# MP-Portenta.net
KiCad netlist of a schematic drawn in Altium Designer
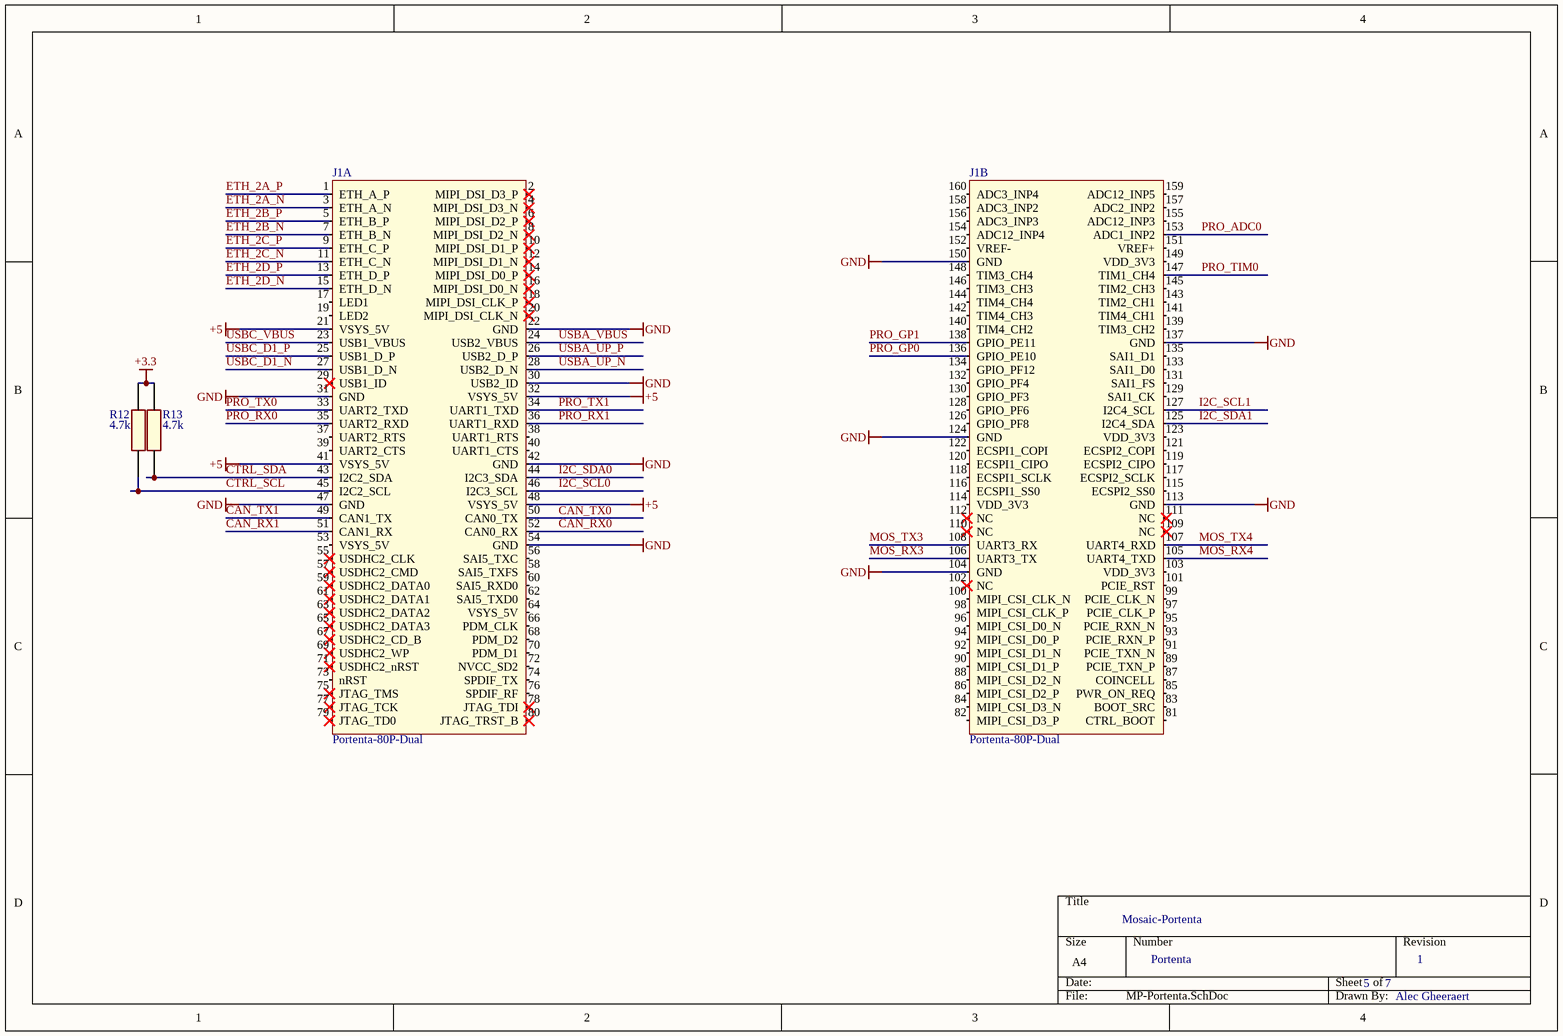
[diagram p0: MP-Portenta.SchDoc]

(export (version "E")
  (design (tool "Eeschema 10.0.6"))
  (components
    (comp (ref "J1")
      (value "Portenta-80P-Dual")
      (footprint "HRS_DF40C-80DP-0.4V(51)")
      (description "80 Pin Arduino Pro")
      (fields (field (name "MANUFACTURER") "Arduino"))
      (libsource (lib "Ghrt") (part "Portenta-80P-Dual"))
    )
    (comp (ref "R12")
      (value "4.7k")
      (footprint "RESC1005X40N")
      (description "0402I 4.7k")
      (fields (field (name "MANUFACTURER") "Walsin") (field (name "TOLERANCE") "1%"))
      (libsource (lib "") (part "WR04X4701FTL_1"))
    )
    (comp (ref "R13")
      (value "4.7k")
      (footprint "RESC1005X40N")
      (description "0402I 4.7k")
      (fields (field (name "MANUFACTURER") "Walsin") (field (name "TOLERANCE") "1%"))
      (libsource (lib "Ghrt") (part "WR04X4701FTL"))
    )
  )
  (nets
    (net (code "1") (name "+3.3") (class "Default")
      (node (ref "R12") (pin "2") (pinfunction "2_2") (pintype "passive"))
      (node (ref "R13") (pin "1") (pinfunction "1_1") (pintype "passive"))
    )
    (net (code "2") (name "+5") (class "Default")
      (node (ref "J1") (pin "21") (pinfunction "VSYS_5V_21") (pintype "passive"))
      (node (ref "J1") (pin "32") (pinfunction "VSYS_5V_32") (pintype "passive"))
      (node (ref "J1") (pin "41") (pinfunction "VSYS_5V_41") (pintype "passive"))
      (node (ref "J1") (pin "48") (pinfunction "VSYS_5V_48") (pintype "passive"))
    )
    (net (code "3") (name "/CAN_RX0") (class "Default")
      (node (ref "J1") (pin "52") (pinfunction "CAN0_RX_52") (pintype "passive"))
    )
    (net (code "4") (name "/CAN_RX1") (class "Default")
      (node (ref "J1") (pin "51") (pinfunction "CAN1_RX_51") (pintype "passive"))
    )
    (net (code "5") (name "/CAN_TX0") (class "Default")
      (node (ref "J1") (pin "50") (pinfunction "CAN0_TX_50") (pintype "passive"))
    )
    (net (code "6") (name "/CAN_TX1") (class "Default")
      (node (ref "J1") (pin "49") (pinfunction "CAN1_TX_49") (pintype "passive"))
    )
    (net (code "7") (name "/CTRL_SCL") (class "Default")
      (node (ref "J1") (pin "45") (pinfunction "I2C2_SCL_45") (pintype "passive"))
      (node (ref "R12") (pin "1") (pinfunction "1_1") (pintype "passive"))
    )
    (net (code "8") (name "/CTRL_SDA") (class "Default")
      (node (ref "J1") (pin "43") (pinfunction "I2C2_SDA_43") (pintype "passive"))
      (node (ref "R13") (pin "2") (pinfunction "2_2") (pintype "passive"))
    )
    (net (code "9") (name "/ETH_2A_N") (class "Default")
      (node (ref "J1") (pin "3") (pinfunction "ETH_A_N_3") (pintype "passive"))
    )
    (net (code "10") (name "/ETH_2A_P") (class "Default")
      (node (ref "J1") (pin "1") (pinfunction "ETH_A_P_1") (pintype "passive"))
    )
    (net (code "11") (name "/ETH_2B_N") (class "Default")
      (node (ref "J1") (pin "7") (pinfunction "ETH_B_N_7") (pintype "passive"))
    )
    (net (code "12") (name "/ETH_2B_P") (class "Default")
      (node (ref "J1") (pin "5") (pinfunction "ETH_B_P_5") (pintype "passive"))
    )
    (net (code "13") (name "/ETH_2C_N") (class "Default")
      (node (ref "J1") (pin "11") (pinfunction "ETH_C_N_11") (pintype "passive"))
    )
    (net (code "14") (name "/ETH_2C_P") (class "Default")
      (node (ref "J1") (pin "9") (pinfunction "ETH_C_P_9") (pintype "passive"))
    )
    (net (code "15") (name "/ETH_2D_N") (class "Default")
      (node (ref "J1") (pin "15") (pinfunction "ETH_D_N_15") (pintype "passive"))
    )
    (net (code "16") (name "/ETH_2D_P") (class "Default")
      (node (ref "J1") (pin "13") (pinfunction "ETH_D_P_13") (pintype "passive"))
    )
    (net (code "17") (name "/I2C_SCL0") (class "Default")
      (node (ref "J1") (pin "46") (pinfunction "I2C3_SCL_46") (pintype "passive"))
    )
    (net (code "18") (name "/I2C_SCL1") (class "Default")
      (node (ref "J1") (pin "127") (pinfunction "I2C4_SCL_127") (pintype "passive"))
    )
    (net (code "19") (name "/I2C_SDA0") (class "Default")
      (node (ref "J1") (pin "44") (pinfunction "I2C3_SDA_44") (pintype "passive"))
    )
    (net (code "20") (name "/I2C_SDA1") (class "Default")
      (node (ref "J1") (pin "125") (pinfunction "I2C4_SDA_125") (pintype "passive"))
    )
    (net (code "21") (name "/MOS_RX3") (class "Default")
      (node (ref "J1") (pin "106") (pinfunction "UART3_TX_106") (pintype "passive"))
    )
    (net (code "22") (name "/MOS_RX4") (class "Default")
      (node (ref "J1") (pin "105") (pinfunction "UART4_TXD_105") (pintype "passive"))
    )
    (net (code "23") (name "/MOS_TX3") (class "Default")
      (node (ref "J1") (pin "108") (pinfunction "UART3_RX_108") (pintype "passive"))
    )
    (net (code "24") (name "/MOS_TX4") (class "Default")
      (node (ref "J1") (pin "107") (pinfunction "UART4_RXD_107") (pintype "passive"))
    )
    (net (code "25") (name "/PRO_ADC0") (class "Default")
      (node (ref "J1") (pin "153") (pinfunction "ADC1_INP2_153") (pintype "passive"))
    )
    (net (code "26") (name "/PRO_GP0") (class "Default")
      (node (ref "J1") (pin "136") (pinfunction "GPIO_PE10_136") (pintype "passive"))
    )
    (net (code "27") (name "/PRO_GP1") (class "Default")
      (node (ref "J1") (pin "138") (pinfunction "GPIO_PE11_138") (pintype "passive"))
    )
    (net (code "28") (name "/PRO_RX0") (class "Default")
      (node (ref "J1") (pin "35") (pinfunction "UART2_RXD_35") (pintype "passive"))
    )
    (net (code "29") (name "/PRO_RX1") (class "Default")
      (node (ref "J1") (pin "36") (pinfunction "UART1_RXD_36") (pintype "passive"))
    )
    (net (code "30") (name "/PRO_TIM0") (class "Default")
      (node (ref "J1") (pin "147") (pinfunction "TIM1_CH4_147") (pintype "passive"))
    )
    (net (code "31") (name "/PRO_TX0") (class "Default")
      (node (ref "J1") (pin "33") (pinfunction "UART2_TXD_33") (pintype "passive"))
    )
    (net (code "32") (name "/PRO_TX1") (class "Default")
      (node (ref "J1") (pin "34") (pinfunction "UART1_TXD_34") (pintype "passive"))
    )
    (net (code "33") (name "/USBA_UP_N") (class "Default")
      (node (ref "J1") (pin "28") (pinfunction "USB2_D_N_28") (pintype "passive"))
    )
    (net (code "34") (name "/USBA_UP_P") (class "Default")
      (node (ref "J1") (pin "26") (pinfunction "USB2_D_P_26") (pintype "passive"))
    )
    (net (code "35") (name "/USBA_VBUS") (class "Default")
      (node (ref "J1") (pin "24") (pinfunction "USB2_VBUS_24") (pintype "passive"))
    )
    (net (code "36") (name "/USBC_D1_N") (class "Default")
      (node (ref "J1") (pin "27") (pinfunction "USB1_D_N_27") (pintype "passive"))
    )
    (net (code "37") (name "/USBC_D1_P") (class "Default")
      (node (ref "J1") (pin "25") (pinfunction "USB1_D_P_25") (pintype "passive"))
    )
    (net (code "38") (name "/USBC_VBUS") (class "Default")
      (node (ref "J1") (pin "23") (pinfunction "USB1_VBUS_23") (pintype "passive"))
    )
    (net (code "39") (name "GND") (class "Default")
      (node (ref "J1") (pin "104") (pinfunction "GND_104") (pintype "passive"))
      (node (ref "J1") (pin "113") (pinfunction "GND_113") (pintype "passive"))
      (node (ref "J1") (pin "124") (pinfunction "GND_124") (pintype "passive"))
      (node (ref "J1") (pin "137") (pinfunction "GND_137") (pintype "passive"))
      (node (ref "J1") (pin "150") (pinfunction "GND_150") (pintype "passive"))
      (node (ref "J1") (pin "22") (pinfunction "GND_22") (pintype "passive"))
      (node (ref "J1") (pin "30") (pinfunction "USB2_ID_30") (pintype "passive"))
      (node (ref "J1") (pin "31") (pinfunction "GND_31") (pintype "passive"))
      (node (ref "J1") (pin "42") (pinfunction "GND_42") (pintype "passive"))
      (node (ref "J1") (pin "47") (pinfunction "GND_47") (pintype "passive"))
      (node (ref "J1") (pin "54") (pinfunction "GND_54") (pintype "passive"))
    )
    (net (code "40") (name "unconnected-(J1A-JTAG_TCK-Pad77)") (class "Default")
      (node (ref "J1") (pin "77") (pinfunction "JTAG_TCK_77") (pintype "passive+no_connect"))
    )
    (net (code "41") (name "unconnected-(J1A-JTAG_TD0-Pad79)") (class "Default")
      (node (ref "J1") (pin "79") (pinfunction "JTAG_TD0_79") (pintype "passive+no_connect"))
    )
    (net (code "42") (name "unconnected-(J1A-JTAG_TDI-Pad78)") (class "Default")
      (node (ref "J1") (pin "78") (pinfunction "JTAG_TDI_78") (pintype "passive+no_connect"))
    )
    (net (code "43") (name "unconnected-(J1A-JTAG_TMS-Pad75)") (class "Default")
      (node (ref "J1") (pin "75") (pinfunction "JTAG_TMS_75") (pintype "passive+no_connect"))
    )
    (net (code "44") (name "unconnected-(J1A-JTAG_TRST_B-Pad80)") (class "Default")
      (node (ref "J1") (pin "80") (pinfunction "JTAG_TRST_B_80") (pintype "passive+no_connect"))
    )
    (net (code "45") (name "unconnected-(J1A-LED1-Pad17)") (class "Default")
      (node (ref "J1") (pin "17") (pinfunction "LED1_17") (pintype "passive"))
    )
    (net (code "46") (name "unconnected-(J1A-LED2-Pad19)") (class "Default")
      (node (ref "J1") (pin "19") (pinfunction "LED2_19") (pintype "passive"))
    )
    (net (code "47") (name "unconnected-(J1A-MIPI_DSI_CLK_N-Pad20)") (class "Default")
      (node (ref "J1") (pin "20") (pinfunction "MIPI_DSI_CLK_N_20") (pintype "passive+no_connect"))
    )
    (net (code "48") (name "unconnected-(J1A-MIPI_DSI_CLK_P-Pad18)") (class "Default")
      (node (ref "J1") (pin "18") (pinfunction "MIPI_DSI_CLK_P_18") (pintype "passive+no_connect"))
    )
    (net (code "49") (name "unconnected-(J1A-MIPI_DSI_D0_N-Pad16)") (class "Default")
      (node (ref "J1") (pin "16") (pinfunction "MIPI_DSI_D0_N_16") (pintype "passive+no_connect"))
    )
    (net (code "50") (name "unconnected-(J1A-MIPI_DSI_D0_P-Pad14)") (class "Default")
      (node (ref "J1") (pin "14") (pinfunction "MIPI_DSI_D0_P_14") (pintype "passive+no_connect"))
    )
    (net (code "51") (name "unconnected-(J1A-MIPI_DSI_D1_N-Pad12)") (class "Default")
      (node (ref "J1") (pin "12") (pinfunction "MIPI_DSI_D1_N_12") (pintype "passive+no_connect"))
    )
    (net (code "52") (name "unconnected-(J1A-MIPI_DSI_D1_P-Pad10)") (class "Default")
      (node (ref "J1") (pin "10") (pinfunction "MIPI_DSI_D1_P_10") (pintype "passive+no_connect"))
    )
    (net (code "53") (name "unconnected-(J1A-MIPI_DSI_D2_N-Pad8)") (class "Default")
      (node (ref "J1") (pin "8") (pinfunction "MIPI_DSI_D2_N_8") (pintype "passive+no_connect"))
    )
    (net (code "54") (name "unconnected-(J1A-MIPI_DSI_D2_P-Pad6)") (class "Default")
      (node (ref "J1") (pin "6") (pinfunction "MIPI_DSI_D2_P_6") (pintype "passive+no_connect"))
    )
    (net (code "55") (name "unconnected-(J1A-MIPI_DSI_D3_N-Pad4)") (class "Default")
      (node (ref "J1") (pin "4") (pinfunction "MIPI_DSI_D3_N_4") (pintype "passive+no_connect"))
    )
    (net (code "56") (name "unconnected-(J1A-MIPI_DSI_D3_P-Pad2)") (class "Default")
      (node (ref "J1") (pin "2") (pinfunction "MIPI_DSI_D3_P_2") (pintype "passive+no_connect"))
    )
    (net (code "57") (name "unconnected-(J1A-NVCC_SD2-Pad72)") (class "Default")
      (node (ref "J1") (pin "72") (pinfunction "NVCC_SD2_72") (pintype "passive"))
    )
    (net (code "58") (name "unconnected-(J1A-PDM_CLK-Pad66)") (class "Default")
      (node (ref "J1") (pin "66") (pinfunction "PDM_CLK_66") (pintype "passive"))
    )
    (net (code "59") (name "unconnected-(J1A-PDM_D1-Pad70)") (class "Default")
      (node (ref "J1") (pin "70") (pinfunction "PDM_D1_70") (pintype "passive"))
    )
    (net (code "60") (name "unconnected-(J1A-PDM_D2-Pad68)") (class "Default")
      (node (ref "J1") (pin "68") (pinfunction "PDM_D2_68") (pintype "passive"))
    )
    (net (code "61") (name "unconnected-(J1A-SAI5_RXD0-Pad60)") (class "Default")
      (node (ref "J1") (pin "60") (pinfunction "SAI5_RXD0_60") (pintype "passive"))
    )
    (net (code "62") (name "unconnected-(J1A-SAI5_TXC-Pad56)") (class "Default")
      (node (ref "J1") (pin "56") (pinfunction "SAI5_TXC_56") (pintype "passive"))
    )
    (net (code "63") (name "unconnected-(J1A-SAI5_TXD0-Pad62)") (class "Default")
      (node (ref "J1") (pin "62") (pinfunction "SAI5_TXD0_62") (pintype "passive"))
    )
    (net (code "64") (name "unconnected-(J1A-SAI5_TXFS-Pad58)") (class "Default")
      (node (ref "J1") (pin "58") (pinfunction "SAI5_TXFS_58") (pintype "passive"))
    )
    (net (code "65") (name "unconnected-(J1A-SPDIF_RF-Pad76)") (class "Default")
      (node (ref "J1") (pin "76") (pinfunction "SPDIF_RF_76") (pintype "passive"))
    )
    (net (code "66") (name "unconnected-(J1A-SPDIF_TX-Pad74)") (class "Default")
      (node (ref "J1") (pin "74") (pinfunction "SPDIF_TX_74") (pintype "passive"))
    )
    (net (code "67") (name "unconnected-(J1A-UART1_CTS-Pad40)") (class "Default")
      (node (ref "J1") (pin "40") (pinfunction "UART1_CTS_40") (pintype "passive"))
    )
    (net (code "68") (name "unconnected-(J1A-UART1_RTS-Pad38)") (class "Default")
      (node (ref "J1") (pin "38") (pinfunction "UART1_RTS_38") (pintype "passive"))
    )
    (net (code "69") (name "unconnected-(J1A-UART2_CTS-Pad39)") (class "Default")
      (node (ref "J1") (pin "39") (pinfunction "UART2_CTS_39") (pintype "passive"))
    )
    (net (code "70") (name "unconnected-(J1A-UART2_RTS-Pad37)") (class "Default")
      (node (ref "J1") (pin "37") (pinfunction "UART2_RTS_37") (pintype "passive"))
    )
    (net (code "71") (name "unconnected-(J1A-USB1_ID-Pad29)") (class "Default")
      (node (ref "J1") (pin "29") (pinfunction "USB1_ID_29") (pintype "passive+no_connect"))
    )
    (net (code "72") (name "unconnected-(J1A-USDHC2_CD_B-Pad67)") (class "Default")
      (node (ref "J1") (pin "67") (pinfunction "USDHC2_CD_B_67") (pintype "passive+no_connect"))
    )
    (net (code "73") (name "unconnected-(J1A-USDHC2_CLK-Pad55)") (class "Default")
      (node (ref "J1") (pin "55") (pinfunction "USDHC2_CLK_55") (pintype "passive+no_connect"))
    )
    (net (code "74") (name "unconnected-(J1A-USDHC2_CMD-Pad57)") (class "Default")
      (node (ref "J1") (pin "57") (pinfunction "USDHC2_CMD_57") (pintype "passive+no_connect"))
    )
    (net (code "75") (name "unconnected-(J1A-USDHC2_DATA0-Pad59)") (class "Default")
      (node (ref "J1") (pin "59") (pinfunction "USDHC2_DATA0_59") (pintype "passive+no_connect"))
    )
    (net (code "76") (name "unconnected-(J1A-USDHC2_DATA1-Pad61)") (class "Default")
      (node (ref "J1") (pin "61") (pinfunction "USDHC2_DATA1_61") (pintype "passive+no_connect"))
    )
    (net (code "77") (name "unconnected-(J1A-USDHC2_DATA2-Pad63)") (class "Default")
      (node (ref "J1") (pin "63") (pinfunction "USDHC2_DATA2_63") (pintype "passive+no_connect"))
    )
    (net (code "78") (name "unconnected-(J1A-USDHC2_DATA3-Pad65)") (class "Default")
      (node (ref "J1") (pin "65") (pinfunction "USDHC2_DATA3_65") (pintype "passive+no_connect"))
    )
    (net (code "79") (name "unconnected-(J1A-USDHC2_WP-Pad69)") (class "Default")
      (node (ref "J1") (pin "69") (pinfunction "USDHC2_WP_69") (pintype "passive+no_connect"))
    )
    (net (code "80") (name "unconnected-(J1A-USDHC2_nRST-Pad71)") (class "Default")
      (node (ref "J1") (pin "71") (pinfunction "USDHC2_nRST_71") (pintype "passive+no_connect"))
    )
    (net (code "81") (name "unconnected-(J1A-VSYS_5V-Pad53)") (class "Default")
      (node (ref "J1") (pin "53") (pinfunction "VSYS_5V_53") (pintype "passive"))
    )
    (net (code "82") (name "unconnected-(J1A-VSYS_5V-Pad64)") (class "Default")
      (node (ref "J1") (pin "64") (pinfunction "VSYS_5V_64") (pintype "passive"))
    )
    (net (code "83") (name "unconnected-(J1A-nRST-Pad73)") (class "Default")
      (node (ref "J1") (pin "73") (pinfunction "nRST_73") (pintype "passive"))
    )
    (net (code "84") (name "unconnected-(J1B-ADC2_INP2-Pad157)") (class "Default")
      (node (ref "J1") (pin "157") (pinfunction "ADC2_INP2_157") (pintype "passive"))
    )
    (net (code "85") (name "unconnected-(J1B-ADC3_INP2-Pad158)") (class "Default")
      (node (ref "J1") (pin "158") (pinfunction "ADC3_INP2_158") (pintype "passive"))
    )
    (net (code "86") (name "unconnected-(J1B-ADC3_INP3-Pad156)") (class "Default")
      (node (ref "J1") (pin "156") (pinfunction "ADC3_INP3_156") (pintype "passive"))
    )
    (net (code "87") (name "unconnected-(J1B-ADC3_INP4-Pad160)") (class "Default")
      (node (ref "J1") (pin "160") (pinfunction "ADC3_INP4_160") (pintype "passive"))
    )
    (net (code "88") (name "unconnected-(J1B-ADC12_INP3-Pad155)") (class "Default")
      (node (ref "J1") (pin "155") (pinfunction "ADC12_INP3_155") (pintype "passive"))
    )
    (net (code "89") (name "unconnected-(J1B-ADC12_INP4-Pad154)") (class "Default")
      (node (ref "J1") (pin "154") (pinfunction "ADC12_INP4_154") (pintype "passive"))
    )
    (net (code "90") (name "unconnected-(J1B-ADC12_INP5-Pad159)") (class "Default")
      (node (ref "J1") (pin "159") (pinfunction "ADC12_INP5_159") (pintype "passive"))
    )
    (net (code "91") (name "unconnected-(J1B-BOOT_SRC-Pad83)") (class "Default")
      (node (ref "J1") (pin "83") (pinfunction "BOOT_SRC_83") (pintype "passive"))
    )
    (net (code "92") (name "unconnected-(J1B-COINCELL-Pad87)") (class "Default")
      (node (ref "J1") (pin "87") (pinfunction "COINCELL_87") (pintype "passive"))
    )
    (net (code "93") (name "unconnected-(J1B-CTRL_BOOT-Pad81)") (class "Default")
      (node (ref "J1") (pin "81") (pinfunction "CTRL_BOOT_81") (pintype "passive"))
    )
    (net (code "94") (name "unconnected-(J1B-ECSPI1_CIPO-Pad120)") (class "Default")
      (node (ref "J1") (pin "120") (pinfunction "ECSPI1_CIPO_120") (pintype "passive"))
    )
    (net (code "95") (name "unconnected-(J1B-ECSPI1_COPI-Pad122)") (class "Default")
      (node (ref "J1") (pin "122") (pinfunction "ECSPI1_COPI_122") (pintype "passive"))
    )
    (net (code "96") (name "unconnected-(J1B-ECSPI1_SCLK-Pad118)") (class "Default")
      (node (ref "J1") (pin "118") (pinfunction "ECSPI1_SCLK_118") (pintype "passive"))
    )
    (net (code "97") (name "unconnected-(J1B-ECSPI1_SS0-Pad116)") (class "Default")
      (node (ref "J1") (pin "116") (pinfunction "ECSPI1_SS0_116") (pintype "passive"))
    )
    (net (code "98") (name "unconnected-(J1B-ECSPI2_CIPO-Pad119)") (class "Default")
      (node (ref "J1") (pin "119") (pinfunction "ECSPI2_CIPO_119") (pintype "passive"))
    )
    (net (code "99") (name "unconnected-(J1B-ECSPI2_COPI-Pad121)") (class "Default")
      (node (ref "J1") (pin "121") (pinfunction "ECSPI2_COPI_121") (pintype "passive"))
    )
    (net (code "100") (name "unconnected-(J1B-ECSPI2_SCLK-Pad117)") (class "Default")
      (node (ref "J1") (pin "117") (pinfunction "ECSPI2_SCLK_117") (pintype "passive"))
    )
    (net (code "101") (name "unconnected-(J1B-ECSPI2_SS0-Pad115)") (class "Default")
      (node (ref "J1") (pin "115") (pinfunction "ECSPI2_SS0_115") (pintype "passive"))
    )
    (net (code "102") (name "unconnected-(J1B-GPIO_PF3-Pad130)") (class "Default")
      (node (ref "J1") (pin "130") (pinfunction "GPIO_PF3_130") (pintype "passive"))
    )
    (net (code "103") (name "unconnected-(J1B-GPIO_PF4-Pad132)") (class "Default")
      (node (ref "J1") (pin "132") (pinfunction "GPIO_PF4_132") (pintype "passive"))
    )
    (net (code "104") (name "unconnected-(J1B-GPIO_PF6-Pad128)") (class "Default")
      (node (ref "J1") (pin "128") (pinfunction "GPIO_PF6_128") (pintype "passive"))
    )
    (net (code "105") (name "unconnected-(J1B-GPIO_PF8-Pad126)") (class "Default")
      (node (ref "J1") (pin "126") (pinfunction "GPIO_PF8_126") (pintype "passive"))
    )
    (net (code "106") (name "unconnected-(J1B-GPIO_PF12-Pad134)") (class "Default")
      (node (ref "J1") (pin "134") (pinfunction "GPIO_PF12_134") (pintype "passive"))
    )
    (net (code "107") (name "unconnected-(J1B-MIPI_CSI_CLK_N-Pad100)") (class "Default")
      (node (ref "J1") (pin "100") (pinfunction "MIPI_CSI_CLK_N_100") (pintype "passive"))
    )
    (net (code "108") (name "unconnected-(J1B-MIPI_CSI_CLK_P-Pad98)") (class "Default")
      (node (ref "J1") (pin "98") (pinfunction "MIPI_CSI_CLK_P_98") (pintype "passive"))
    )
    (net (code "109") (name "unconnected-(J1B-MIPI_CSI_D0_N-Pad96)") (class "Default")
      (node (ref "J1") (pin "96") (pinfunction "MIPI_CSI_D0_N_96") (pintype "passive"))
    )
    (net (code "110") (name "unconnected-(J1B-MIPI_CSI_D0_P-Pad94)") (class "Default")
      (node (ref "J1") (pin "94") (pinfunction "MIPI_CSI_D0_P_94") (pintype "passive"))
    )
    (net (code "111") (name "unconnected-(J1B-MIPI_CSI_D1_N-Pad92)") (class "Default")
      (node (ref "J1") (pin "92") (pinfunction "MIPI_CSI_D1_N_92") (pintype "passive"))
    )
    (net (code "112") (name "unconnected-(J1B-MIPI_CSI_D1_P-Pad90)") (class "Default")
      (node (ref "J1") (pin "90") (pinfunction "MIPI_CSI_D1_P_90") (pintype "passive"))
    )
    (net (code "113") (name "unconnected-(J1B-MIPI_CSI_D2_N-Pad88)") (class "Default")
      (node (ref "J1") (pin "88") (pinfunction "MIPI_CSI_D2_N_88") (pintype "passive"))
    )
    (net (code "114") (name "unconnected-(J1B-MIPI_CSI_D2_P-Pad86)") (class "Default")
      (node (ref "J1") (pin "86") (pinfunction "MIPI_CSI_D2_P_86") (pintype "passive"))
    )
    (net (code "115") (name "unconnected-(J1B-MIPI_CSI_D3_N-Pad84)") (class "Default")
      (node (ref "J1") (pin "84") (pinfunction "MIPI_CSI_D3_N_84") (pintype "passive"))
    )
    (net (code "116") (name "unconnected-(J1B-MIPI_CSI_D3_P-Pad82)") (class "Default")
      (node (ref "J1") (pin "82") (pinfunction "MIPI_CSI_D3_P_82") (pintype "passive"))
    )
    (net (code "117") (name "unconnected-(J1B-NC-Pad102)") (class "Default")
      (node (ref "J1") (pin "102") (pinfunction "NC_102") (pintype "passive+no_connect"))
    )
    (net (code "118") (name "unconnected-(J1B-NC-Pad109)") (class "Default")
      (node (ref "J1") (pin "109") (pinfunction "NC_109") (pintype "passive+no_connect"))
    )
    (net (code "119") (name "unconnected-(J1B-NC-Pad110)") (class "Default")
      (node (ref "J1") (pin "110") (pinfunction "NC_110") (pintype "passive+no_connect"))
    )
    (net (code "120") (name "unconnected-(J1B-NC-Pad111)") (class "Default")
      (node (ref "J1") (pin "111") (pinfunction "NC_111") (pintype "passive+no_connect"))
    )
    (net (code "121") (name "unconnected-(J1B-NC-Pad112)") (class "Default")
      (node (ref "J1") (pin "112") (pinfunction "NC_112") (pintype "passive+no_connect"))
    )
    (net (code "122") (name "unconnected-(J1B-PCIE_CLK_N-Pad99)") (class "Default")
      (node (ref "J1") (pin "99") (pinfunction "PCIE_CLK_N_99") (pintype "passive"))
    )
    (net (code "123") (name "unconnected-(J1B-PCIE_CLK_P-Pad97)") (class "Default")
      (node (ref "J1") (pin "97") (pinfunction "PCIE_CLK_P_97") (pintype "passive"))
    )
    (net (code "124") (name "unconnected-(J1B-PCIE_RST-Pad101)") (class "Default")
      (node (ref "J1") (pin "101") (pinfunction "PCIE_RST_101") (pintype "passive"))
    )
    (net (code "125") (name "unconnected-(J1B-PCIE_RXN_N-Pad95)") (class "Default")
      (node (ref "J1") (pin "95") (pinfunction "PCIE_RXN_N_95") (pintype "passive"))
    )
    (net (code "126") (name "unconnected-(J1B-PCIE_RXN_P-Pad93)") (class "Default")
      (node (ref "J1") (pin "93") (pinfunction "PCIE_RXN_P_93") (pintype "passive"))
    )
    (net (code "127") (name "unconnected-(J1B-PCIE_TXN_N-Pad91)") (class "Default")
      (node (ref "J1") (pin "91") (pinfunction "PCIE_TXN_N_91") (pintype "passive"))
    )
    (net (code "128") (name "unconnected-(J1B-PCIE_TXN_P-Pad89)") (class "Default")
      (node (ref "J1") (pin "89") (pinfunction "PCIE_TXN_P_89") (pintype "passive"))
    )
    (net (code "129") (name "unconnected-(J1B-PWR_ON_REQ-Pad85)") (class "Default")
      (node (ref "J1") (pin "85") (pinfunction "PWR_ON_REQ_85") (pintype "passive"))
    )
    (net (code "130") (name "unconnected-(J1B-SAI1_CK-Pad129)") (class "Default")
      (node (ref "J1") (pin "129") (pinfunction "SAI1_CK_129") (pintype "passive"))
    )
    (net (code "131") (name "unconnected-(J1B-SAI1_D0-Pad133)") (class "Default")
      (node (ref "J1") (pin "133") (pinfunction "SAI1_D0_133") (pintype "passive"))
    )
    (net (code "132") (name "unconnected-(J1B-SAI1_D1-Pad135)") (class "Default")
      (node (ref "J1") (pin "135") (pinfunction "SAI1_D1_135") (pintype "passive"))
    )
    (net (code "133") (name "unconnected-(J1B-SAI1_FS-Pad131)") (class "Default")
      (node (ref "J1") (pin "131") (pinfunction "SAI1_FS_131") (pintype "passive"))
    )
    (net (code "134") (name "unconnected-(J1B-TIM2_CH1-Pad143)") (class "Default")
      (node (ref "J1") (pin "143") (pinfunction "TIM2_CH1_143") (pintype "passive"))
    )
    (net (code "135") (name "unconnected-(J1B-TIM2_CH3-Pad145)") (class "Default")
      (node (ref "J1") (pin "145") (pinfunction "TIM2_CH3_145") (pintype "passive"))
    )
    (net (code "136") (name "unconnected-(J1B-TIM3_CH2-Pad139)") (class "Default")
      (node (ref "J1") (pin "139") (pinfunction "TIM3_CH2_139") (pintype "passive"))
    )
    (net (code "137") (name "unconnected-(J1B-TIM3_CH3-Pad146)") (class "Default")
      (node (ref "J1") (pin "146") (pinfunction "TIM3_CH3_146") (pintype "passive"))
    )
    (net (code "138") (name "unconnected-(J1B-TIM3_CH4-Pad148)") (class "Default")
      (node (ref "J1") (pin "148") (pinfunction "TIM3_CH4_148") (pintype "passive"))
    )
    (net (code "139") (name "unconnected-(J1B-TIM4_CH1-Pad141)") (class "Default")
      (node (ref "J1") (pin "141") (pinfunction "TIM4_CH1_141") (pintype "passive"))
    )
    (net (code "140") (name "unconnected-(J1B-TIM4_CH2-Pad140)") (class "Default")
      (node (ref "J1") (pin "140") (pinfunction "TIM4_CH2_140") (pintype "passive"))
    )
    (net (code "141") (name "unconnected-(J1B-TIM4_CH3-Pad142)") (class "Default")
      (node (ref "J1") (pin "142") (pinfunction "TIM4_CH3_142") (pintype "passive"))
    )
    (net (code "142") (name "unconnected-(J1B-TIM4_CH4-Pad144)") (class "Default")
      (node (ref "J1") (pin "144") (pinfunction "TIM4_CH4_144") (pintype "passive"))
    )
    (net (code "143") (name "unconnected-(J1B-VDD_3V3-Pad103)") (class "Default")
      (node (ref "J1") (pin "103") (pinfunction "VDD_3V3_103") (pintype "passive"))
    )
    (net (code "144") (name "unconnected-(J1B-VDD_3V3-Pad114)") (class "Default")
      (node (ref "J1") (pin "114") (pinfunction "VDD_3V3_114") (pintype "passive"))
    )
    (net (code "145") (name "unconnected-(J1B-VDD_3V3-Pad123)") (class "Default")
      (node (ref "J1") (pin "123") (pinfunction "VDD_3V3_123") (pintype "passive"))
    )
    (net (code "146") (name "unconnected-(J1B-VDD_3V3-Pad149)") (class "Default")
      (node (ref "J1") (pin "149") (pinfunction "VDD_3V3_149") (pintype "passive"))
    )
    (net (code "147") (name "unconnected-(J1B-VREF+-Pad151)") (class "Default")
      (node (ref "J1") (pin "151") (pinfunction "VREF+_151") (pintype "passive"))
    )
    (net (code "148") (name "unconnected-(J1B-VREF--Pad152)") (class "Default")
      (node (ref "J1") (pin "152") (pinfunction "VREF-_152") (pintype "passive"))
    )
  )
)
